# MCU.net
KiCad netlist of a schematic drawn in Altium Designer
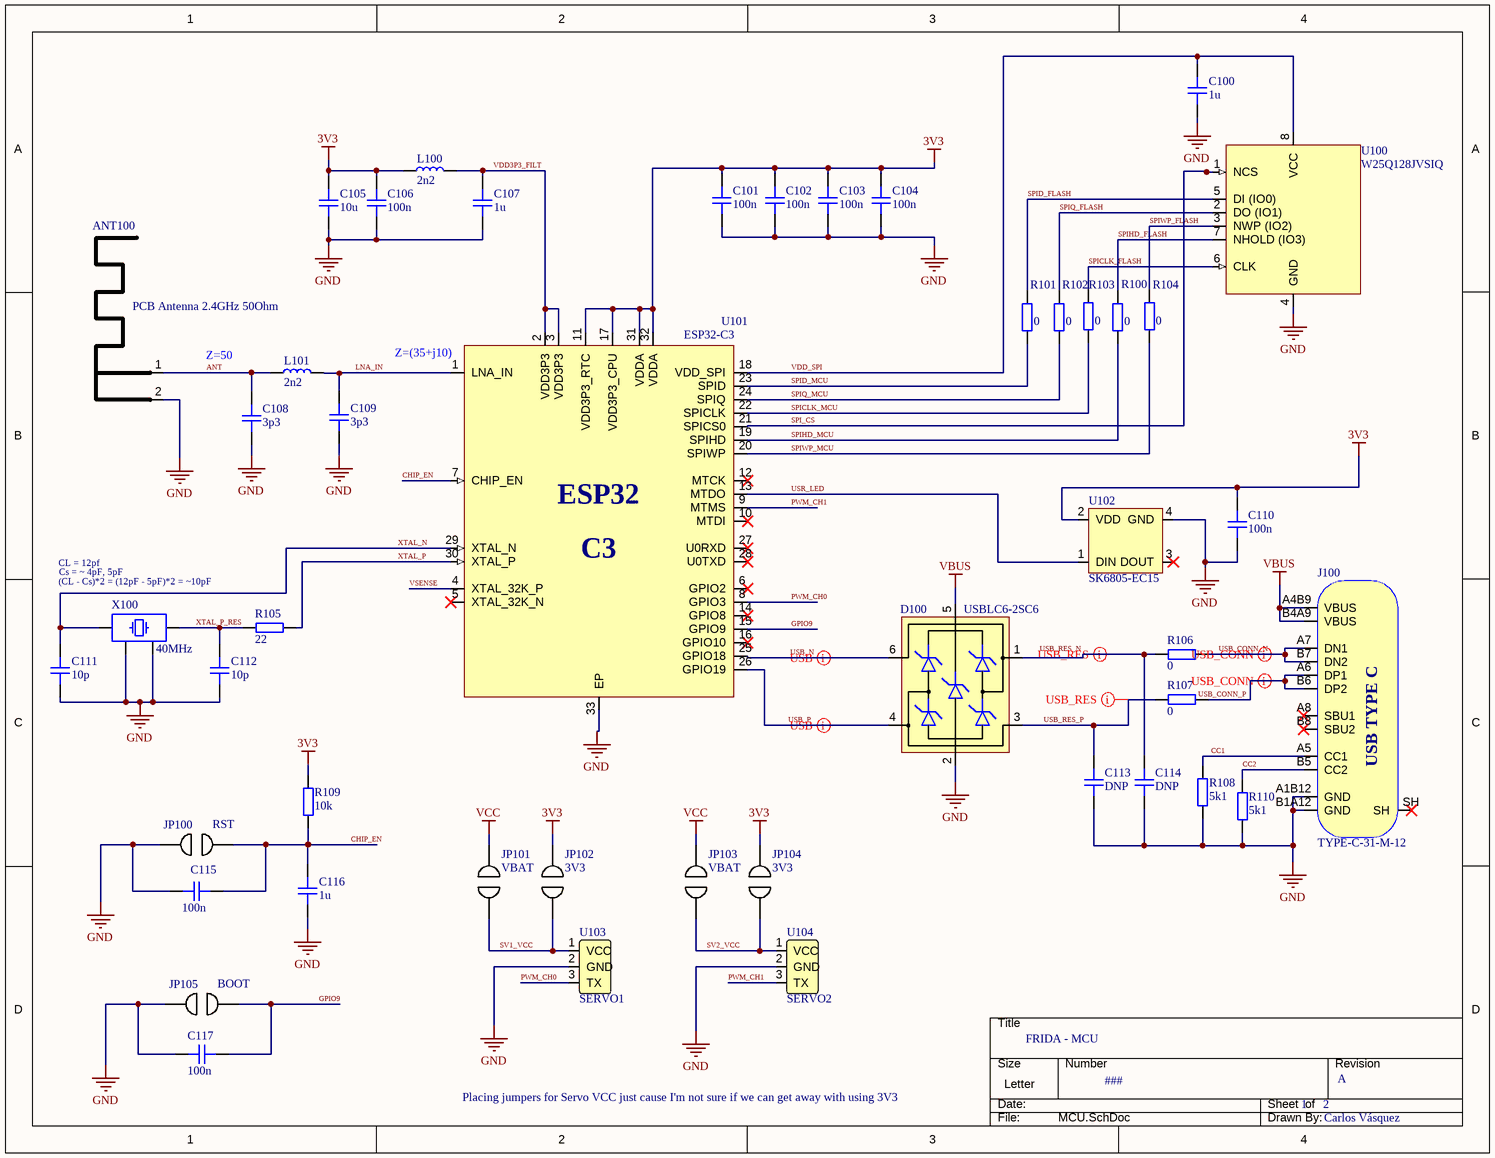
[diagram p0: MCU.SchDoc]

(export (version "E")
  (design (tool "Eeschema 10.0.6"))
  (components
    (comp (ref "ANT100")
      (value "PCB Antenna 2.4GHz 50Ohm")
      (footprint "ANT_IFA_USB_2_4GHZ_50R")
      (description "Inverted F 2.4GHz ISM PCB Antenna 50 Ohm")
      (libsource (lib "Schematic-Lib-PhilsLab") (part "ANT_IFA_USB_2_4GHZ_50R"))
    )
    (comp (ref "C100")
      (value "1u")
      (footprint "CAP_0402")
      (description "Capacitor SMD 0402")
      (libsource (lib "Schematic-Lib-PhilsLab") (part "CAP_0402"))
    )
    (comp (ref "C101")
      (value "100n")
      (footprint "CAP_0402")
      (description "Capacitor SMD 0402")
      (libsource (lib "Schematic-Lib-PhilsLab") (part "CAP_0402"))
    )
    (comp (ref "C102")
      (value "100n")
      (footprint "CAP_0402")
      (description "Capacitor SMD 0402")
      (libsource (lib "Schematic-Lib-PhilsLab") (part "CAP_0402"))
    )
    (comp (ref "C103")
      (value "100n")
      (footprint "CAP_0402")
      (description "Capacitor SMD 0402")
      (libsource (lib "Schematic-Lib-PhilsLab") (part "CAP_0402"))
    )
    (comp (ref "C104")
      (value "100n")
      (footprint "CAP_0402")
      (description "Capacitor SMD 0402")
      (libsource (lib "Schematic-Lib-PhilsLab") (part "CAP_0402"))
    )
    (comp (ref "C105")
      (value "10u")
      (footprint "CAP_0603")
      (description "Capacitor SMD 0603")
      (libsource (lib "Schematic-Lib-PhilsLab") (part "CAP_0603"))
    )
    (comp (ref "C106")
      (value "100n")
      (footprint "CAP_0402")
      (description "Capacitor SMD 0402")
      (libsource (lib "Schematic-Lib-PhilsLab") (part "CAP_0402"))
    )
    (comp (ref "C107")
      (value "1u")
      (footprint "CAP_0402")
      (description "Capacitor SMD 0402")
      (libsource (lib "Schematic-Lib-PhilsLab") (part "CAP_0402"))
    )
    (comp (ref "C108")
      (value "3p3")
      (footprint "CAP_0402")
      (description "Capacitor SMD 0402")
      (libsource (lib "Schematic-Lib-PhilsLab") (part "CAP_0402"))
    )
    (comp (ref "C109")
      (value "3p3")
      (footprint "CAP_0402")
      (description "Capacitor SMD 0402")
      (libsource (lib "Schematic-Lib-PhilsLab") (part "CAP_0402"))
    )
    (comp (ref "C110")
      (value "100n")
      (footprint "CAP_0402")
      (description "Capacitor SMD 0402")
      (libsource (lib "Schematic-Lib-PhilsLab") (part "CAP_0402"))
    )
    (comp (ref "C111")
      (value "10p")
      (footprint "CAP_0402")
      (description "Capacitor SMD 0402")
      (libsource (lib "Schematic-Lib-PhilsLab") (part "CAP_0402"))
    )
    (comp (ref "C112")
      (value "10p")
      (footprint "CAP_0402")
      (description "Capacitor SMD 0402")
      (libsource (lib "Schematic-Lib-PhilsLab") (part "CAP_0402"))
    )
    (comp (ref "C113")
      (value "DNP")
      (footprint "CAP_0603")
      (description "Capacitor SMD 0603")
      (libsource (lib "Schematic-Lib-PhilsLab") (part "CAP_0603"))
    )
    (comp (ref "C114")
      (value "DNP")
      (footprint "CAP_0603")
      (description "Capacitor SMD 0603")
      (libsource (lib "Schematic-Lib-PhilsLab") (part "CAP_0603"))
    )
    (comp (ref "C115")
      (value "100n")
      (footprint "CAP_0402")
      (description "Capacitor SMD 0402")
      (libsource (lib "Schematic-Lib-PhilsLab") (part "CAP_0402"))
    )
    (comp (ref "C116")
      (value "1u")
      (footprint "CAP_0402")
      (description "Capacitor SMD 0402")
      (libsource (lib "Schematic-Lib-PhilsLab") (part "CAP_0402"))
    )
    (comp (ref "C117")
      (value "100n")
      (footprint "CAP_0402")
      (description "Capacitor SMD 0402")
      (libsource (lib "Schematic-Lib-PhilsLab") (part "CAP_0402"))
    )
    (comp (ref "D100")
      (value "USBLC6-2SC6")
      (footprint "SOT-23-6")
      (description "Low-Capacitance ESD Protection USB")
      (fields (field (name "MANUFACTURER") "STMicroelectronics"))
      (libsource (lib "Schematic-Lib-PhilsLab") (part "USBLC6-2SC6"))
    )
    (comp (ref "J100")
      (value "TYPE-C-31-M-12")
      (footprint "TYPE-C-31-M-12")
      (description "USB Type C Connector Horizontal SMT")
      (fields (field (name "MANUFACTURER") "Koren Hroparts"))
      (libsource (lib "Schematic-Lib-PhilsLab") (part "TYPE-C-31-M-12"))
    )
    (comp (ref "JP100")
      (value "RST")
      (footprint "SOLDER JUMPER BRIDGE")
      (description "Solder Jumper Bridge")
      (libsource (lib "TerreneitorLib") (part "SOLDER BRIDGE"))
    )
    (comp (ref "JP101")
      (value "VBAT")
      (footprint "SOLDER JUMPER BRIDGE")
      (description "Solder Jumper Bridge")
      (libsource (lib "TerreneitorLib") (part "SOLDER BRIDGE"))
    )
    (comp (ref "JP102")
      (value "3V3")
      (footprint "SOLDER JUMPER BRIDGE")
      (description "Solder Jumper Bridge")
      (libsource (lib "TerreneitorLib") (part "SOLDER BRIDGE"))
    )
    (comp (ref "JP103")
      (value "VBAT")
      (footprint "SOLDER JUMPER BRIDGE")
      (description "Solder Jumper Bridge")
      (libsource (lib "TerreneitorLib") (part "SOLDER BRIDGE"))
    )
    (comp (ref "JP104")
      (value "3V3")
      (footprint "SOLDER JUMPER BRIDGE")
      (description "Solder Jumper Bridge")
      (libsource (lib "TerreneitorLib") (part "SOLDER BRIDGE"))
    )
    (comp (ref "JP105")
      (value "BOOT")
      (footprint "SOLDER JUMPER BRIDGE")
      (description "Solder Jumper Bridge")
      (libsource (lib "TerreneitorLib") (part "SOLDER BRIDGE"))
    )
    (comp (ref "L100")
      (value "2n2")
      (footprint "IND_0402")
      (description "Inductor SMD 0402")
      (libsource (lib "Schematic-Lib-PhilsLab") (part "IND_0402"))
    )
    (comp (ref "L101")
      (value "2n2")
      (footprint "IND_0402")
      (description "Inductor SMD 0402")
      (libsource (lib "Schematic-Lib-PhilsLab") (part "IND_0402"))
    )
    (comp (ref "R100")
      (value "0")
      (footprint "RES_0402")
      (description "Resistor SMD 0402")
      (libsource (lib "Schematic-Lib-PhilsLab") (part "RES_0402"))
    )
    (comp (ref "R101")
      (value "0")
      (footprint "RES_0402")
      (description "Resistor SMD 0402")
      (libsource (lib "Schematic-Lib-PhilsLab") (part "RES_0402"))
    )
    (comp (ref "R102")
      (value "0")
      (footprint "RES_0402")
      (description "Resistor SMD 0402")
      (libsource (lib "Schematic-Lib-PhilsLab") (part "RES_0402"))
    )
    (comp (ref "R103")
      (value "0")
      (footprint "RES_0402")
      (description "Resistor SMD 0402")
      (libsource (lib "Schematic-Lib-PhilsLab") (part "RES_0402"))
    )
    (comp (ref "R104")
      (value "0")
      (footprint "RES_0402")
      (description "Resistor SMD 0402")
      (libsource (lib "Schematic-Lib-PhilsLab") (part "RES_0402"))
    )
    (comp (ref "R105")
      (value "22")
      (footprint "RES_0402")
      (description "Resistor SMD 0402")
      (libsource (lib "Schematic-Lib-PhilsLab") (part "RES_0402"))
    )
    (comp (ref "R106")
      (value "0")
      (footprint "RES_0402")
      (description "Resistor SMD 0402")
      (libsource (lib "Schematic-Lib-PhilsLab") (part "RES_0402"))
    )
    (comp (ref "R107")
      (value "0")
      (footprint "RES_0402")
      (description "Resistor SMD 0402")
      (libsource (lib "Schematic-Lib-PhilsLab") (part "RES_0402"))
    )
    (comp (ref "R108")
      (value "5k1")
      (footprint "RES_0402")
      (description "Resistor SMD 0402")
      (libsource (lib "Schematic-Lib-PhilsLab") (part "RES_0402"))
    )
    (comp (ref "R109")
      (value "10k")
      (footprint "RES_0402")
      (description "Resistor SMD 0402")
      (libsource (lib "Schematic-Lib-PhilsLab") (part "RES_0402"))
    )
    (comp (ref "R110")
      (value "5k1")
      (footprint "RES_0402")
      (description "Resistor SMD 0402")
      (libsource (lib "Schematic-Lib-PhilsLab") (part "RES_0402"))
    )
    (comp (ref "U100")
      (value "W25Q128JVSIQ")
      (footprint "SOIC8_208 mil")
      (description "128M-BIT\r\nSERIAL FLASH MEMORY WITH\r\nDUAL/QUAD SPI & QPI & DTR SOIC-8 208 MIL")
      (fields
        (field (name "MANUFACTURER") "Winbond")
        (field (name "MANUFACTURER PART NUMBER") "W25Q128JVSIM")
      )
      (libsource (lib "Schematic-Lib-PhilsLab") (part "W25Q128JVSIQ"))
    )
    (comp (ref "U101")
      (value "ESP32-C3")
      (footprint "QFN32-5x5")
      (fields (field (name "MANUFACTURER") "Espressif"))
      (libsource (lib "Schematic-Lib-PhilsLab") (part "ESP32-C3"))
    )
    (comp (ref "U102")
      (value "SK6805-EC15")
      (footprint "SK6805-EC15")
      (libsource (lib "TerreneitorLib") (part "SK6805-EC15"))
    )
    (comp (ref "U103")
      (value "SERVO1")
      (footprint "GPS UART HEADER")
      (description "UART GPS (3 pin breakout)")
      (libsource (lib "TerreneitorLib") (part "UART GPS"))
    )
    (comp (ref "U104")
      (value "SERVO2")
      (footprint "GPS UART HEADER")
      (description "UART GPS (3 pin breakout)")
      (libsource (lib "TerreneitorLib") (part "UART GPS"))
    )
    (comp (ref "X100")
      (value "40MHz")
      (footprint "XTAL_3225")
      (description "Crystal SMD 40MHz 10PPM 12pF 3225")
      (fields
        (field (name "MANUFACTURER") "Epson")
        (field (name "MANUFACTURER PART NUMBER") "TSX-3225 24.0000MF15X-AC")
      )
      (libsource (lib "Schematic-Lib-PhilsLab") (part "TSX-3225_24.0000MF15X-AC"))
    )
  )
  (nets
    (net (code "1") (name "/ANT") (class "Default")
      (node (ref "ANT100") (pin "1") (pinfunction "RF_1") (pintype "passive"))
      (node (ref "C108") (pin "2") (pinfunction "2_2") (pintype "passive"))
      (node (ref "L101") (pin "1") (pinfunction "1_1") (pintype "passive"))
    )
    (net (code "2") (name "/CC1") (class "Default")
      (node (ref "J100") (pin "A5") (pinfunction "CC1_A5") (pintype "passive"))
      (node (ref "R108") (pin "2") (pinfunction "2_2") (pintype "passive"))
    )
    (net (code "3") (name "/CC2") (class "Default")
      (node (ref "J100") (pin "B5") (pinfunction "CC2_B5") (pintype "tri_state"))
      (node (ref "R110") (pin "2") (pinfunction "2_2") (pintype "passive"))
    )
    (net (code "4") (name "/CHIP_EN") (class "Default")
      (node (ref "C115") (pin "1") (pinfunction "1_1") (pintype "passive"))
      (node (ref "C116") (pin "2") (pinfunction "2_2") (pintype "passive"))
      (node (ref "JP100") (pin "2") (pinfunction "2_2") (pintype "passive"))
      (node (ref "R109") (pin "1") (pinfunction "1_1") (pintype "passive"))
      (node (ref "U101") (pin "7") (pinfunction "CHIP_EN_7") (pintype "input"))
    )
    (net (code "5") (name "/GPIO9") (class "Default")
      (node (ref "C117") (pin "1") (pinfunction "1_1") (pintype "passive"))
      (node (ref "JP105") (pin "2") (pinfunction "2_2") (pintype "passive"))
      (node (ref "U101") (pin "15") (pinfunction "GPIO9_15") (pintype "bidirectional"))
    )
    (net (code "6") (name "/LNA_IN") (class "Default")
      (node (ref "C109") (pin "2") (pinfunction "2_2") (pintype "passive"))
      (node (ref "L101") (pin "2") (pinfunction "2_2") (pintype "passive"))
      (node (ref "U101") (pin "1") (pinfunction "LNA_IN_1") (pintype "bidirectional"))
    )
    (net (code "7") (name "/PWM_CH0") (class "Default")
      (node (ref "U101") (pin "8") (pinfunction "GPIO3_8") (pintype "bidirectional"))
      (node (ref "U103") (pin "3") (pinfunction "TX_3") (pintype "passive"))
    )
    (net (code "8") (name "/PWM_CH1") (class "Default")
      (node (ref "U101") (pin "9") (pinfunction "MTMS_9") (pintype "bidirectional"))
      (node (ref "U104") (pin "3") (pinfunction "TX_3") (pintype "passive"))
    )
    (net (code "9") (name "/SPICLK_FLASH") (class "Default")
      (node (ref "R103") (pin "2") (pinfunction "2_2") (pintype "passive"))
      (node (ref "U100") (pin "6") (pinfunction "CLK_6") (pintype "input"))
    )
    (net (code "10") (name "/SPICLK_MCU") (class "Default")
      (node (ref "R103") (pin "1") (pinfunction "1_1") (pintype "passive"))
      (node (ref "U101") (pin "22") (pinfunction "SPICLK_22") (pintype "bidirectional"))
    )
    (net (code "11") (name "/SPID_FLASH") (class "Default")
      (node (ref "R101") (pin "2") (pinfunction "2_2") (pintype "passive"))
      (node (ref "U100") (pin "5") (pinfunction "DI_(IO0)_5") (pintype "bidirectional"))
    )
    (net (code "12") (name "/SPID_MCU") (class "Default")
      (node (ref "R101") (pin "1") (pinfunction "1_1") (pintype "passive"))
      (node (ref "U101") (pin "23") (pinfunction "SPID_23") (pintype "bidirectional"))
    )
    (net (code "13") (name "/SPIHD_FLASH") (class "Default")
      (node (ref "R100") (pin "2") (pinfunction "2_2") (pintype "passive"))
      (node (ref "U100") (pin "7") (pinfunction "NHOLD_(IO3)_7") (pintype "bidirectional"))
    )
    (net (code "14") (name "/SPIHD_MCU") (class "Default")
      (node (ref "R100") (pin "1") (pinfunction "1_1") (pintype "passive"))
      (node (ref "U101") (pin "19") (pinfunction "SPIHD_19") (pintype "bidirectional"))
    )
    (net (code "15") (name "/SPIQ_FLASH") (class "Default")
      (node (ref "R102") (pin "2") (pinfunction "2_2") (pintype "passive"))
      (node (ref "U100") (pin "2") (pinfunction "DO_(IO1)_2") (pintype "bidirectional"))
    )
    (net (code "16") (name "/SPIQ_MCU") (class "Default")
      (node (ref "R102") (pin "1") (pinfunction "1_1") (pintype "passive"))
      (node (ref "U101") (pin "24") (pinfunction "SPIQ_24") (pintype "bidirectional"))
    )
    (net (code "17") (name "/SPIWP_FLASH") (class "Default")
      (node (ref "R104") (pin "2") (pinfunction "2_2") (pintype "passive"))
      (node (ref "U100") (pin "3") (pinfunction "NWP_(IO2)_3") (pintype "bidirectional"))
    )
    (net (code "18") (name "/SPIWP_MCU") (class "Default")
      (node (ref "R104") (pin "1") (pinfunction "1_1") (pintype "passive"))
      (node (ref "U101") (pin "20") (pinfunction "SPIWP_20") (pintype "bidirectional"))
    )
    (net (code "19") (name "/SPI_CS") (class "Default")
      (node (ref "U100") (pin "1") (pinfunction "NCS_1") (pintype "input"))
      (node (ref "U101") (pin "21") (pinfunction "SPICS0_21") (pintype "bidirectional"))
    )
    (net (code "20") (name "/SV1_VCC") (class "Default")
      (node (ref "JP101") (pin "1") (pinfunction "1_1") (pintype "passive"))
      (node (ref "JP102") (pin "1") (pinfunction "1_1") (pintype "passive"))
      (node (ref "U103") (pin "1") (pinfunction "VCC_1") (pintype "passive"))
    )
    (net (code "21") (name "/SV2_VCC") (class "Default")
      (node (ref "JP103") (pin "1") (pinfunction "1_1") (pintype "passive"))
      (node (ref "JP104") (pin "1") (pinfunction "1_1") (pintype "passive"))
      (node (ref "U104") (pin "1") (pinfunction "VCC_1") (pintype "passive"))
    )
    (net (code "22") (name "/USB_CONN_N") (class "Default")
      (node (ref "J100") (pin "A7") (pinfunction "DN1_A7") (pintype "bidirectional"))
      (node (ref "J100") (pin "B7") (pinfunction "DN2_B7") (pintype "bidirectional"))
      (node (ref "R106") (pin "2") (pinfunction "2_2") (pintype "passive"))
    )
    (net (code "23") (name "/USB_CONN_P") (class "Default")
      (node (ref "J100") (pin "A6") (pinfunction "DP1_A6") (pintype "bidirectional"))
      (node (ref "J100") (pin "B6") (pinfunction "DP2_B6") (pintype "bidirectional"))
      (node (ref "R107") (pin "2") (pinfunction "2_2") (pintype "passive"))
    )
    (net (code "24") (name "/USB_N") (class "Default")
      (node (ref "D100") (pin "6") (pinfunction "IO1_6") (pintype "bidirectional"))
      (node (ref "U101") (pin "25") (pinfunction "GPIO18_25") (pintype "bidirectional"))
    )
    (net (code "25") (name "/USB_P") (class "Default")
      (node (ref "D100") (pin "4") (pinfunction "IO2_4") (pintype "bidirectional"))
      (node (ref "U101") (pin "26") (pinfunction "GPIO19_26") (pintype "bidirectional"))
    )
    (net (code "26") (name "/USB_RES_N") (class "Default")
      (node (ref "C114") (pin "2") (pinfunction "2_2") (pintype "passive"))
      (node (ref "D100") (pin "1") (pinfunction "IO1_1") (pintype "bidirectional"))
      (node (ref "R106") (pin "1") (pinfunction "1_1") (pintype "passive"))
    )
    (net (code "27") (name "/USB_RES_P") (class "Default")
      (node (ref "C113") (pin "2") (pinfunction "2_2") (pintype "passive"))
      (node (ref "D100") (pin "3") (pinfunction "IO2_3") (pintype "bidirectional"))
      (node (ref "R107") (pin "1") (pinfunction "1_1") (pintype "passive"))
    )
    (net (code "28") (name "/USR_LED") (class "Default")
      (node (ref "U101") (pin "13") (pinfunction "MTDO_13") (pintype "bidirectional"))
      (node (ref "U102") (pin "1") (pinfunction "DIN_1") (pintype "passive"))
    )
    (net (code "29") (name "/VDD3P3_FILT") (class "Default")
      (node (ref "C107") (pin "2") (pinfunction "2_2") (pintype "passive"))
      (node (ref "L100") (pin "2") (pinfunction "2_2") (pintype "passive"))
      (node (ref "U101") (pin "2") (pinfunction "VDD3P3_2") (pintype "power_in"))
      (node (ref "U101") (pin "3") (pinfunction "VDD3P3_3") (pintype "power_in"))
    )
    (net (code "30") (name "/VDD_SPI") (class "Default")
      (node (ref "C100") (pin "2") (pinfunction "2_2") (pintype "passive"))
      (node (ref "U100") (pin "8") (pinfunction "VCC_8") (pintype "power_in"))
      (node (ref "U101") (pin "18") (pinfunction "VDD_SPI_18") (pintype "power_in"))
    )
    (net (code "31") (name "/VSENSE") (class "Default")
      (node (ref "U101") (pin "4") (pinfunction "XTAL_32K_P_4") (pintype "bidirectional"))
    )
    (net (code "32") (name "/XTAL_N") (class "Default")
      (node (ref "C111") (pin "1") (pinfunction "1_1") (pintype "passive"))
      (node (ref "U101") (pin "29") (pinfunction "XTAL_N_29") (pintype "input"))
      (node (ref "X100") (pin "1") (pinfunction "1_1") (pintype "passive"))
    )
    (net (code "33") (name "/XTAL_P") (class "Default")
      (node (ref "R105") (pin "2") (pinfunction "2_2") (pintype "passive"))
      (node (ref "U101") (pin "30") (pinfunction "XTAL_P_30") (pintype "input"))
    )
    (net (code "34") (name "/XTAL_P_RES") (class "Default")
      (node (ref "C112") (pin "1") (pinfunction "1_1") (pintype "passive"))
      (node (ref "R105") (pin "1") (pinfunction "1_1") (pintype "passive"))
      (node (ref "X100") (pin "3") (pinfunction "3_3") (pintype "passive"))
    )
    (net (code "35") (name "3V3") (class "Default")
      (node (ref "C101") (pin "1") (pinfunction "1_1") (pintype "passive"))
      (node (ref "C102") (pin "1") (pinfunction "1_1") (pintype "passive"))
      (node (ref "C103") (pin "1") (pinfunction "1_1") (pintype "passive"))
      (node (ref "C104") (pin "1") (pinfunction "1_1") (pintype "passive"))
      (node (ref "C105") (pin "1") (pinfunction "1_1") (pintype "passive"))
      (node (ref "C106") (pin "1") (pinfunction "1_1") (pintype "passive"))
      (node (ref "C110") (pin "2") (pinfunction "2_2") (pintype "passive"))
      (node (ref "JP102") (pin "2") (pinfunction "2_2") (pintype "passive"))
      (node (ref "JP104") (pin "2") (pinfunction "2_2") (pintype "passive"))
      (node (ref "L100") (pin "1") (pinfunction "1_1") (pintype "passive"))
      (node (ref "R109") (pin "2") (pinfunction "2_2") (pintype "passive"))
      (node (ref "U101") (pin "11") (pinfunction "VDD3P3_RTC_11") (pintype "power_in"))
      (node (ref "U101") (pin "17") (pinfunction "VDD3P3_CPU_17") (pintype "power_in"))
      (node (ref "U101") (pin "31") (pinfunction "VDDA_31") (pintype "power_in"))
      (node (ref "U101") (pin "32") (pinfunction "VDDA_32") (pintype "power_in"))
      (node (ref "U102") (pin "2") (pinfunction "VDD_2") (pintype "passive"))
    )
    (net (code "36") (name "GND") (class "Default")
      (node (ref "ANT100") (pin "2") (pinfunction "GND_2") (pintype "passive"))
      (node (ref "C100") (pin "1") (pinfunction "1_1") (pintype "passive"))
      (node (ref "C101") (pin "2") (pinfunction "2_2") (pintype "passive"))
      (node (ref "C102") (pin "2") (pinfunction "2_2") (pintype "passive"))
      (node (ref "C103") (pin "2") (pinfunction "2_2") (pintype "passive"))
      (node (ref "C104") (pin "2") (pinfunction "2_2") (pintype "passive"))
      (node (ref "C105") (pin "2") (pinfunction "2_2") (pintype "passive"))
      (node (ref "C106") (pin "2") (pinfunction "2_2") (pintype "passive"))
      (node (ref "C107") (pin "1") (pinfunction "1_1") (pintype "passive"))
      (node (ref "C108") (pin "1") (pinfunction "1_1") (pintype "passive"))
      (node (ref "C109") (pin "1") (pinfunction "1_1") (pintype "passive"))
      (node (ref "C110") (pin "1") (pinfunction "1_1") (pintype "passive"))
      (node (ref "C111") (pin "2") (pinfunction "2_2") (pintype "passive"))
      (node (ref "C112") (pin "2") (pinfunction "2_2") (pintype "passive"))
      (node (ref "C113") (pin "1") (pinfunction "1_1") (pintype "passive"))
      (node (ref "C114") (pin "1") (pinfunction "1_1") (pintype "passive"))
      (node (ref "C115") (pin "2") (pinfunction "2_2") (pintype "passive"))
      (node (ref "C116") (pin "1") (pinfunction "1_1") (pintype "passive"))
      (node (ref "C117") (pin "2") (pinfunction "2_2") (pintype "passive"))
      (node (ref "D100") (pin "2") (pinfunction "GND_2") (pintype "power_in"))
      (node (ref "J100") (pin "A1B12") (pinfunction "GND_A1B12") (pintype "power_in"))
      (node (ref "J100") (pin "B1A12") (pinfunction "GND_B1A12") (pintype "power_in"))
      (node (ref "JP100") (pin "1") (pinfunction "1_1") (pintype "passive"))
      (node (ref "JP105") (pin "1") (pinfunction "1_1") (pintype "passive"))
      (node (ref "R108") (pin "1") (pinfunction "1_1") (pintype "passive"))
      (node (ref "R110") (pin "1") (pinfunction "1_1") (pintype "passive"))
      (node (ref "U100") (pin "4") (pinfunction "GND_4") (pintype "power_in"))
      (node (ref "U101") (pin "33") (pinfunction "EP_33") (pintype "power_in"))
      (node (ref "U102") (pin "4") (pinfunction "GND_4") (pintype "passive"))
      (node (ref "U103") (pin "2") (pinfunction "GND_2") (pintype "passive"))
      (node (ref "U104") (pin "2") (pinfunction "GND_2") (pintype "passive"))
      (node (ref "X100") (pin "2") (pinfunction "2_2") (pintype "passive"))
      (node (ref "X100") (pin "4") (pinfunction "4_4") (pintype "passive"))
    )
    (net (code "37") (name "VBUS") (class "Default")
      (node (ref "D100") (pin "5") (pinfunction "VBUS_5") (pintype "power_in"))
      (node (ref "J100") (pin "A4B9") (pinfunction "VBUS_A4B9") (pintype "power_in"))
      (node (ref "J100") (pin "B4A9") (pinfunction "VBUS_B4A9") (pintype "power_in"))
    )
    (net (code "38") (name "VCC") (class "Default")
      (node (ref "JP101") (pin "2") (pinfunction "2_2") (pintype "passive"))
      (node (ref "JP103") (pin "2") (pinfunction "2_2") (pintype "passive"))
    )
    (net (code "39") (name "unconnected-(J100-PadSH)") (class "Default")
      (node (ref "J100") (pin "SH") (pinfunction "SH_SH") (pintype "power_in+no_connect"))
    )
    (net (code "40") (name "unconnected-(J100-SBU1-PadA8)") (class "Default")
      (node (ref "J100") (pin "A8") (pinfunction "SBU1_A8") (pintype "bidirectional+no_connect"))
    )
    (net (code "41") (name "unconnected-(J100-SBU2-PadB8)") (class "Default")
      (node (ref "J100") (pin "B8") (pinfunction "SBU2_B8") (pintype "bidirectional+no_connect"))
    )
    (net (code "42") (name "unconnected-(U101-GPIO2-Pad6)") (class "Default")
      (node (ref "U101") (pin "6") (pinfunction "GPIO2_6") (pintype "bidirectional+no_connect"))
    )
    (net (code "43") (name "unconnected-(U101-GPIO8-Pad14)") (class "Default")
      (node (ref "U101") (pin "14") (pinfunction "GPIO8_14") (pintype "bidirectional+no_connect"))
    )
    (net (code "44") (name "unconnected-(U101-GPIO10-Pad16)") (class "Default")
      (node (ref "U101") (pin "16") (pinfunction "GPIO10_16") (pintype "bidirectional+no_connect"))
    )
    (net (code "45") (name "unconnected-(U101-MTCK-Pad12)") (class "Default")
      (node (ref "U101") (pin "12") (pinfunction "MTCK_12") (pintype "bidirectional+no_connect"))
    )
    (net (code "46") (name "unconnected-(U101-MTDI-Pad10)") (class "Default")
      (node (ref "U101") (pin "10") (pinfunction "MTDI_10") (pintype "bidirectional+no_connect"))
    )
    (net (code "47") (name "unconnected-(U101-U0RXD-Pad27)") (class "Default")
      (node (ref "U101") (pin "27") (pinfunction "U0RXD_27") (pintype "bidirectional+no_connect"))
    )
    (net (code "48") (name "unconnected-(U101-U0TXD-Pad28)") (class "Default")
      (node (ref "U101") (pin "28") (pinfunction "U0TXD_28") (pintype "bidirectional+no_connect"))
    )
    (net (code "49") (name "unconnected-(U101-XTAL_32K_N-Pad5)") (class "Default")
      (node (ref "U101") (pin "5") (pinfunction "XTAL_32K_N_5") (pintype "bidirectional+no_connect"))
    )
    (net (code "50") (name "unconnected-(U102-DOUT-Pad3)") (class "Default")
      (node (ref "U102") (pin "3") (pinfunction "DOUT_3") (pintype "passive+no_connect"))
    )
  )
)
